# InhalerCap.net
KiCad netlist of a schematic drawn in Altium Designer
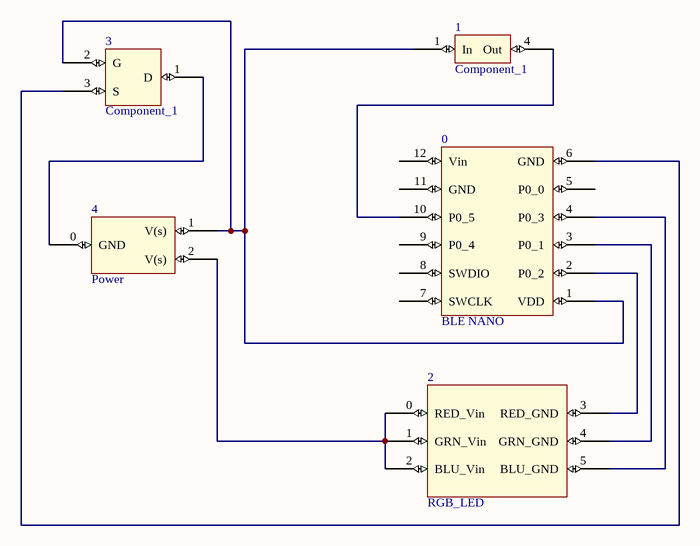
[diagram p0: InhalerCap.SchDoc]

(export (version "E")
  (design (tool "Eeschema 10.0.6"))
  (components
    (comp (ref "0") (value "BLE NANO") (footprint "BLE_NANO") (libsource (lib "Schlib1") (part "BLE NANO")))
    (comp (ref "1")
      (value "Component_1")
      (footprint "Button")
      (libsource (lib "SkinnyPushButton") (part "Component_1"))
    )
    (comp (ref "2") (value "RGB_LED") (footprint "BIG_LED") (libsource (lib "RGB_LED") (part "RGB_LED")))
    (comp (ref "3")
      (value "Component_1")
      (footprint "MOSFET_3_PIN")
      (libsource (lib "DIODE") (part "Component_1"))
    )
    (comp (ref "4")
      (value "Power")
      (footprint "CR2032_Holder")
      (libsource (lib "CoinCellBatteryHolder") (part "Coin_Cell_Battery_Holder"))
    )
  )
  (nets
    (net (code "1") (name "Net-(0-P0_1)") (class "Default")
      (node (ref "0") (pin "3") (pinfunction "P0_1_3") (pintype "bidirectional"))
      (node (ref "2") (pin "4") (pinfunction "GRN_GND_4") (pintype "bidirectional"))
    )
    (net (code "2") (name "Net-(0-P0_2)") (class "Default")
      (node (ref "0") (pin "2") (pinfunction "P0_2_2") (pintype "bidirectional"))
      (node (ref "2") (pin "3") (pinfunction "RED_GND_3") (pintype "bidirectional"))
    )
    (net (code "3") (name "Net-(0-P0_3)") (class "Default")
      (node (ref "0") (pin "4") (pinfunction "P0_3_4") (pintype "bidirectional"))
      (node (ref "2") (pin "5") (pinfunction "BLU_GND_5") (pintype "bidirectional"))
    )
    (net (code "4") (name "Net-(0-P0_5)") (class "Default")
      (node (ref "0") (pin "10") (pinfunction "P0_5_10") (pintype "bidirectional"))
      (node (ref "1") (pin "4") (pinfunction "Out_4") (pintype "bidirectional"))
    )
    (net (code "5") (name "Net-(0-VDD)") (class "Default")
      (node (ref "0") (pin "1") (pinfunction "VDD_1") (pintype "bidirectional"))
      (node (ref "1") (pin "1") (pinfunction "In_1") (pintype "bidirectional"))
      (node (ref "3") (pin "2") (pinfunction "G_2") (pintype "bidirectional"))
      (node (ref "4") (pin "1") (pinfunction "V(s)_1") (pintype "bidirectional"))
    )
    (net (code "6") (name "Net-(2-BLU_Vin)") (class "Default")
      (node (ref "2") (pin "0") (pinfunction "RED_Vin_0") (pintype "bidirectional"))
      (node (ref "2") (pin "1") (pinfunction "GRN_Vin_1") (pintype "bidirectional"))
      (node (ref "2") (pin "2") (pinfunction "BLU_Vin_2") (pintype "bidirectional"))
      (node (ref "4") (pin "2") (pinfunction "V(s)_2") (pintype "bidirectional"))
    )
    (net (code "7") (name "Net-(3-D)") (class "Default")
      (node (ref "3") (pin "1") (pinfunction "D_1") (pintype "bidirectional"))
      (node (ref "4") (pin "0") (pinfunction "GND_0") (pintype "bidirectional"))
    )
    (net (code "8") (name "Net-(3-S)") (class "Default")
      (node (ref "0") (pin "6") (pinfunction "GND_6") (pintype "bidirectional"))
      (node (ref "3") (pin "3") (pinfunction "S_3") (pintype "bidirectional"))
    )
    (net (code "9") (name "unconnected-(0-GND-Pad11)") (class "Default")
      (node (ref "0") (pin "11") (pinfunction "GND_11") (pintype "bidirectional"))
    )
    (net (code "10") (name "unconnected-(0-P0_0-Pad5)") (class "Default")
      (node (ref "0") (pin "5") (pinfunction "P0_0_5") (pintype "bidirectional"))
    )
    (net (code "11") (name "unconnected-(0-P0_4-Pad9)") (class "Default")
      (node (ref "0") (pin "9") (pinfunction "P0_4_9") (pintype "bidirectional"))
    )
    (net (code "12") (name "unconnected-(0-SWCLK-Pad7)") (class "Default")
      (node (ref "0") (pin "7") (pinfunction "SWCLK_7") (pintype "bidirectional"))
    )
    (net (code "13") (name "unconnected-(0-SWDIO-Pad8)") (class "Default")
      (node (ref "0") (pin "8") (pinfunction "SWDIO_8") (pintype "bidirectional"))
    )
    (net (code "14") (name "unconnected-(0-Vin-Pad12)") (class "Default")
      (node (ref "0") (pin "12") (pinfunction "Vin_12") (pintype "bidirectional"))
    )
  )
)
